# design.net
KiCad netlist of a schematic drawn in Altium Designer
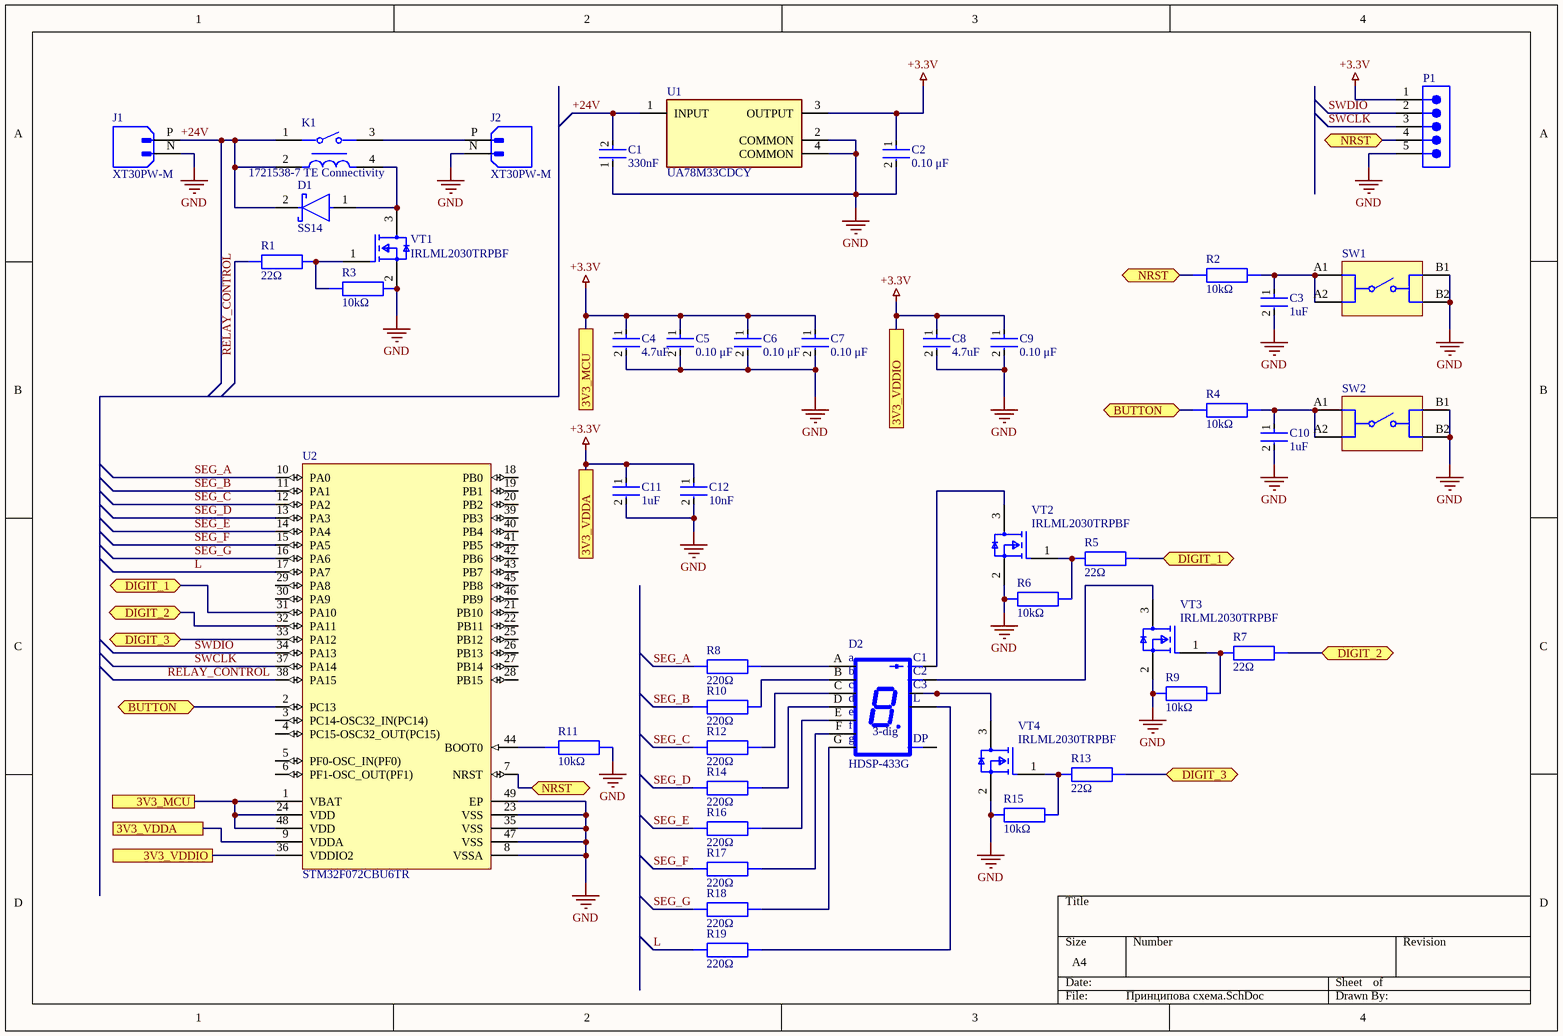
[diagram p0: Принципова схема.SchDoc]

(export (version "E")
  (design (tool "Eeschema 10.0.6"))
  (components
    (comp (ref "C1")
      (value "330nF")
      (footprint "FP-C1608-080-0_1-IPC_B")
      (description "Multilayer Ceramic Capacitors 330nF ±20% 35V X5R SMD 0603")
      (fields (field (name "TOLERANCE") "20%"))
      (libsource (lib "Altium Content Vault") (part "236180d848d6139a670b325ea6854c9"))
    )
    (comp (ref "C2")
      (value "0.10 μF")
      (footprint "FP-C0603C-CF-IPC_B")
      (description "CAP CER 0.1UF 50V X7R 0603")
      (fields
        (field (name "MANUFACTURER") "KEMET")
        (field (name "OCTOPART") "https://octopart.com/c0603c104j5racauto-kemet-18804944")
      )
      (libsource (lib "Altium Content Vault") (part "b4654b650e69147ec39a6b967a45e02"))
    )
    (comp (ref "C3")
      (value "1uF")
      (footprint "FP-0603-L_1_6_0_1-W_0_8_0-IPC_A")
      (description "None")
      (fields (field (name "TOLERANCE") "20%"))
      (libsource (lib "Altium Content Vault") (part "02cd4be3c70576c341d710602a673aa"))
    )
    (comp (ref "C4")
      (value "4.7uF")
      (footprint "FP-0603-L_1_6_0_1-W_0_8_0-IPC_B")
      (description "None")
      (fields (field (name "VOLTAGE") "6.3V") (field (name "TOLERANCE") "20%"))
      (libsource (lib "Altium Content Vault") (part "11868f565c42a9108669ba33697ecf6"))
    )
    (comp (ref "C5")
      (value "0.10 μF")
      (footprint "FP-C0603C-CF-IPC_B")
      (description "CAP CER 0.1UF 50V X7R 0603")
      (fields
        (field (name "MANUFACTURER") "KEMET")
        (field (name "OCTOPART") "https://octopart.com/c0603c104j5racauto-kemet-18804944")
      )
      (libsource (lib "Altium Content Vault") (part "b4654b650e69147ec39a6b967a45e02"))
    )
    (comp (ref "C6")
      (value "0.10 μF")
      (footprint "FP-C0603C-CF-IPC_B")
      (description "CAP CER 0.1UF 50V X7R 0603")
      (fields
        (field (name "MANUFACTURER") "KEMET")
        (field (name "OCTOPART") "https://octopart.com/c0603c104j5racauto-kemet-18804944")
      )
      (libsource (lib "Altium Content Vault") (part "b4654b650e69147ec39a6b967a45e02"))
    )
    (comp (ref "C7")
      (value "0.10 μF")
      (footprint "FP-C0603C-CF-IPC_B")
      (description "CAP CER 0.1UF 50V X7R 0603")
      (fields
        (field (name "MANUFACTURER") "KEMET")
        (field (name "OCTOPART") "https://octopart.com/c0603c104j5racauto-kemet-18804944")
      )
      (libsource (lib "Altium Content Vault") (part "b4654b650e69147ec39a6b967a45e02"))
    )
    (comp (ref "C8")
      (value "4.7uF")
      (footprint "FP-0603-L_1_6_0_1-W_0_8_0-IPC_B")
      (description "None")
      (fields (field (name "VOLTAGE") "6.3V") (field (name "TOLERANCE") "20%"))
      (libsource (lib "Altium Content Vault") (part "11868f565c42a9108669ba33697ecf6"))
    )
    (comp (ref "C9")
      (value "0.10 μF")
      (footprint "FP-C0603C-CF-IPC_B")
      (description "CAP CER 0.1UF 50V X7R 0603")
      (fields
        (field (name "MANUFACTURER") "KEMET")
        (field (name "OCTOPART") "https://octopart.com/c0603c104j5racauto-kemet-18804944")
      )
      (libsource (lib "Altium Content Vault") (part "b4654b650e69147ec39a6b967a45e02"))
    )
    (comp (ref "C10")
      (value "1uF")
      (footprint "FP-0603-L_1_6_0_1-W_0_8_0-IPC_A")
      (description "None")
      (fields (field (name "TOLERANCE") "20%"))
      (libsource (lib "Altium Content Vault") (part "02cd4be3c70576c341d710602a673aa"))
    )
    (comp (ref "C11")
      (value "1uF")
      (footprint "FP-0603-L_1_6_0_1-W_0_8_0-IPC_A")
      (description "None")
      (fields (field (name "TOLERANCE") "20%"))
      (libsource (lib "Altium Content Vault") (part "02cd4be3c70576c341d710602a673aa"))
    )
    (comp (ref "C12")
      (value "10nF")
      (footprint "FP-0603-L_1_6_0_1-W_0_8_0-IPC_A")
      (description "None")
      (fields (field (name "TOLERANCE") "10%"))
      (libsource (lib "Altium Content Vault") (part "02cd4be3c70576c341d710602a673aa"))
    )
    (comp (ref "D1")
      (value "SS14")
      (footprint "FP-403AE-MFG")
      (description "DIODE SCHOTTKY 40V 1A SMA")
      (fields
        (field (name "MANUFACTURER") "ON Semiconductor")
        (field (name "OCTOPART") "https://octopart.com/ss14-on+semiconductor-29205033")
      )
      (libsource (lib "Altium Content Vault") (part "360ad2f4ac25a952324d13796385471"))
    )
    (comp (ref "D2")
      (value "HDSP-433G")
      (footprint "HDSP-433G")
      (fields (field (name "MF") "Broadcom Limited") (field (name "DIGI-KEY_PART_NUMBER") "516-3125-ND"))
      (libsource (lib "HDSP-433G") (part "HDSP-433G"))
    )
    (comp (ref "J1")
      (value "XT30PW-M")
      (footprint "AMASS_XT30PW-M:AMASS_XT30PW-M")
      (description "Socket; DC supply; XT30; male; PIN: 2; on PCBs; THT; Colour: yellow")
      (fields (field (name "MANUFACTURER") "AMASS"))
      (libsource (lib "TestTask-Hardware") (part "XT30PW-M"))
    )
    (comp (ref "J2")
      (value "XT30PW-M")
      (footprint "AMASS_XT30PW-M:AMASS_XT30PW-M")
      (description "Socket; DC supply; XT30; male; PIN: 2; on PCBs; THT; Colour: yellow")
      (fields (field (name "MANUFACTURER") "AMASS"))
      (libsource (lib "") (part "XT30PW-M_1"))
    )
    (comp (ref "K1")
      (value "1721538-7 TE Connectivity")
      (footprint "FP-1721538-7-MFG")
      (description "RELAY GEN PURPOSE SPST10A 24V")
      (libsource (lib "Altium Content Vault") (part "efdf740da079d6e8343da2175463948"))
    )
    (comp (ref "P1")
      (value "~")
      (footprint "61300511121")
      (description "THT Vertical Pin Header WR-PHD, Pitch 2.54 mm, Single Row, 5 pins")
      (libsource (lib "Altium Content Vault") (part "Header_Male_1R_05P"))
    )
    (comp (ref "R1")
      (value "22Ω")
      (footprint "RES 0603_1608")
      (description "Fixed Resistor, Metal Glaze/Thick Film, 0.1W, 22ohm, 75V, 5% +/-Tol, Surface Mount, 0603")
      (fields
        (field (name "MANUFACTURER") "Vishay")
        (field (name "MANUFACTURER PART NUMBER") "CRCW060322R0JNTA")
      )
      (libsource (lib "Res") (part "Resistor"))
    )
    (comp (ref "R2")
      (value "10kΩ")
      (footprint "RES 0603_1608")
      (description "Res Thick Film 0603 10K Ohm 5% 0.1W(1/10W) ±200ppm/C Pad SMD Automotive T/R")
      (fields
        (field (name "MANUFACTURER") "Vishay")
        (field (name "MANUFACTURER PART NUMBER") "CRCW060310K0JNTA")
      )
      (libsource (lib "Res") (part "Resistor"))
    )
    (comp (ref "R3")
      (value "10kΩ")
      (footprint "RES 0603_1608")
      (description "Res Thick Film 0603 10K Ohm 5% 0.1W(1/10W) ±200ppm/C Pad SMD Automotive T/R")
      (fields
        (field (name "MANUFACTURER") "Vishay")
        (field (name "MANUFACTURER PART NUMBER") "CRCW060310K0JNTA")
      )
      (libsource (lib "Res") (part "Resistor"))
    )
    (comp (ref "R4")
      (value "10kΩ")
      (footprint "RES 0603_1608")
      (description "Res Thick Film 0603 10K Ohm 5% 0.1W(1/10W) ±200ppm/C Pad SMD Automotive T/R")
      (fields
        (field (name "MANUFACTURER") "Vishay")
        (field (name "MANUFACTURER PART NUMBER") "CRCW060310K0JNTA")
      )
      (libsource (lib "Res") (part "Resistor"))
    )
    (comp (ref "R5")
      (value "22Ω")
      (footprint "RES 0603_1608")
      (description "Fixed Resistor, Metal Glaze/Thick Film, 0.1W, 22ohm, 75V, 5% +/-Tol, Surface Mount, 0603")
      (fields
        (field (name "MANUFACTURER") "Vishay")
        (field (name "MANUFACTURER PART NUMBER") "CRCW060322R0JNTA")
      )
      (libsource (lib "Res") (part "Resistor"))
    )
    (comp (ref "R6")
      (value "10kΩ")
      (footprint "RES 0603_1608")
      (description "Res Thick Film 0603 10K Ohm 5% 0.1W(1/10W) ±200ppm/C Pad SMD Automotive T/R")
      (fields
        (field (name "MANUFACTURER") "Vishay")
        (field (name "MANUFACTURER PART NUMBER") "CRCW060310K0JNTA")
      )
      (libsource (lib "Res") (part "Resistor"))
    )
    (comp (ref "R7")
      (value "22Ω")
      (footprint "RES 0603_1608")
      (description "Fixed Resistor, Metal Glaze/Thick Film, 0.1W, 22ohm, 75V, 5% +/-Tol, Surface Mount, 0603")
      (fields
        (field (name "MANUFACTURER") "Vishay")
        (field (name "MANUFACTURER PART NUMBER") "CRCW060322R0JNTA")
      )
      (libsource (lib "Res") (part "Resistor"))
    )
    (comp (ref "R8")
      (value "220Ω")
      (footprint "RES 0603_1608")
      (description "Res Thick Film 0603 220 Ohm 1% 0.1W(1/10W) ±100ppm/C Pad SMD T/R Automotive AEC-Q200")
      (fields
        (field (name "MANUFACTURER") "Vishay")
        (field (name "MANUFACTURER PART NUMBER") "CRCW0603220RFKEC")
      )
      (libsource (lib "Res") (part "Resistor"))
    )
    (comp (ref "R9")
      (value "10kΩ")
      (footprint "RES 0603_1608")
      (description "Res Thick Film 0603 10K Ohm 5% 0.1W(1/10W) ±200ppm/C Pad SMD Automotive T/R")
      (fields
        (field (name "MANUFACTURER") "Vishay")
        (field (name "MANUFACTURER PART NUMBER") "CRCW060310K0JNTA")
      )
      (libsource (lib "Res") (part "Resistor"))
    )
    (comp (ref "R10")
      (value "220Ω")
      (footprint "RES 0603_1608")
      (description "Res Thick Film 0603 220 Ohm 1% 0.1W(1/10W) ±100ppm/C Pad SMD T/R Automotive AEC-Q200")
      (fields
        (field (name "MANUFACTURER") "Vishay")
        (field (name "MANUFACTURER PART NUMBER") "CRCW0603220RFKEC")
      )
      (libsource (lib "Res") (part "Resistor"))
    )
    (comp (ref "R11")
      (value "10kΩ")
      (footprint "RES 0603_1608")
      (description "Res Thick Film 0603 10K Ohm 5% 0.1W(1/10W) ±200ppm/C Pad SMD Automotive T/R")
      (fields
        (field (name "MANUFACTURER") "Vishay")
        (field (name "MANUFACTURER PART NUMBER") "CRCW060310K0JNTA")
      )
      (libsource (lib "Res") (part "Resistor"))
    )
    (comp (ref "R12")
      (value "220Ω")
      (footprint "RES 0603_1608")
      (description "Res Thick Film 0603 220 Ohm 1% 0.1W(1/10W) ±100ppm/C Pad SMD T/R Automotive AEC-Q200")
      (fields
        (field (name "MANUFACTURER") "Vishay")
        (field (name "MANUFACTURER PART NUMBER") "CRCW0603220RFKEC")
      )
      (libsource (lib "Res") (part "Resistor"))
    )
    (comp (ref "R13")
      (value "22Ω")
      (footprint "RES 0603_1608")
      (description "Fixed Resistor, Metal Glaze/Thick Film, 0.1W, 22ohm, 75V, 5% +/-Tol, Surface Mount, 0603")
      (fields
        (field (name "MANUFACTURER") "Vishay")
        (field (name "MANUFACTURER PART NUMBER") "CRCW060322R0JNTA")
      )
      (libsource (lib "Res") (part "Resistor"))
    )
    (comp (ref "R14")
      (value "220Ω")
      (footprint "RES 0603_1608")
      (description "Res Thick Film 0603 220 Ohm 1% 0.1W(1/10W) ±100ppm/C Pad SMD T/R Automotive AEC-Q200")
      (fields
        (field (name "MANUFACTURER") "Vishay")
        (field (name "MANUFACTURER PART NUMBER") "CRCW0603220RFKEC")
      )
      (libsource (lib "Res") (part "Resistor"))
    )
    (comp (ref "R15")
      (value "10kΩ")
      (footprint "RES 0603_1608")
      (description "Res Thick Film 0603 10K Ohm 5% 0.1W(1/10W) ±200ppm/C Pad SMD Automotive T/R")
      (fields
        (field (name "MANUFACTURER") "Vishay")
        (field (name "MANUFACTURER PART NUMBER") "CRCW060310K0JNTA")
      )
      (libsource (lib "Res") (part "Resistor"))
    )
    (comp (ref "R16")
      (value "220Ω")
      (footprint "RES 0603_1608")
      (description "Res Thick Film 0603 220 Ohm 1% 0.1W(1/10W) ±100ppm/C Pad SMD T/R Automotive AEC-Q200")
      (fields
        (field (name "MANUFACTURER") "Vishay")
        (field (name "MANUFACTURER PART NUMBER") "CRCW0603220RFKEC")
      )
      (libsource (lib "Res") (part "Resistor"))
    )
    (comp (ref "R17")
      (value "220Ω")
      (footprint "RES 0603_1608")
      (description "Res Thick Film 0603 220 Ohm 1% 0.1W(1/10W) ±100ppm/C Pad SMD T/R Automotive AEC-Q200")
      (fields
        (field (name "MANUFACTURER") "Vishay")
        (field (name "MANUFACTURER PART NUMBER") "CRCW0603220RFKEC")
      )
      (libsource (lib "Res") (part "Resistor"))
    )
    (comp (ref "R18")
      (value "220Ω")
      (footprint "RES 0603_1608")
      (description "Res Thick Film 0603 220 Ohm 1% 0.1W(1/10W) ±100ppm/C Pad SMD T/R Automotive AEC-Q200")
      (fields
        (field (name "MANUFACTURER") "Vishay")
        (field (name "MANUFACTURER PART NUMBER") "CRCW0603220RFKEC")
      )
      (libsource (lib "Res") (part "Resistor"))
    )
    (comp (ref "R19")
      (value "220Ω")
      (footprint "RES 0603_1608")
      (description "Res Thick Film 0603 220 Ohm 1% 0.1W(1/10W) ±100ppm/C Pad SMD T/R Automotive AEC-Q200")
      (fields
        (field (name "MANUFACTURER") "Vishay")
        (field (name "MANUFACTURER PART NUMBER") "CRCW0603220RFKEC")
      )
      (libsource (lib "Res") (part "Resistor"))
    )
    (comp (ref "SW1")
      (value "430162043826")
      (footprint "430162043826")
      (description "Tactile Switch, 0.05A, 12Vdc, 260Gf, Smd Rohs Compliant: Yes")
      (libsource (lib "Altium Content Vault") (part "SPST-NO_4P"))
    )
    (comp (ref "SW2")
      (value "430162043826")
      (footprint "430162043826")
      (description "Tactile Switch, 0.05A, 12Vdc, 260Gf, Smd Rohs Compliant: Yes")
      (libsource (lib "Altium Content Vault") (part "SPST-NO_4P"))
    )
    (comp (ref "U1")
      (value "UA78M33CDCY")
      (footprint "FP-DCY0004A-MFG")
      (description "IC REG LIN 3.3V 500MA SOT223-4")
      (fields
        (field (name "OCTOPART") "https://octopart.com/ua78m33cdcy-texas+instruments-1010398")
        (field (name "MANUFACTURER") "Texas Instruments")
      )
      (libsource (lib "Altium Content Vault") (part "be96c08bf657505148608e930dbb0d1"))
    )
    (comp (ref "U2")
      (value "STM32F072CBU6TR")
      (footprint "STM-UFQFPN48_L")
      (libsource (lib "Altium Content Vault") (part "MC-ARM-STM32F072-UFQFPN48"))
    )
    (comp (ref "VT1")
      (value "IRLML2030TRPBF")
      (footprint "FP-Micro3-MFG")
      (description "MOSFET N-CH 30V 2.7A SOT-23-3")
      (fields
        (field (name "OCTOPART") "https://octopart.com/irlml2030trpbf-infineon-65874966")
        (field (name "MANUFACTURER") "Infineon")
      )
      (libsource (lib "Altium Content Vault") (part "0a9ea7c96deaaede766a5b531c28de0"))
    )
    (comp (ref "VT2")
      (value "IRLML2030TRPBF")
      (footprint "FP-Micro3-MFG")
      (description "MOSFET N-CH 30V 2.7A SOT-23-3")
      (fields
        (field (name "OCTOPART") "https://octopart.com/irlml2030trpbf-infineon-65874966")
        (field (name "MANUFACTURER") "Infineon")
      )
      (libsource (lib "Altium Content Vault") (part "0a9ea7c96deaaede766a5b531c28de0"))
    )
    (comp (ref "VT3")
      (value "IRLML2030TRPBF")
      (footprint "FP-Micro3-MFG")
      (description "MOSFET N-CH 30V 2.7A SOT-23-3")
      (fields
        (field (name "OCTOPART") "https://octopart.com/irlml2030trpbf-infineon-65874966")
        (field (name "MANUFACTURER") "Infineon")
      )
      (libsource (lib "Altium Content Vault") (part "0a9ea7c96deaaede766a5b531c28de0"))
    )
    (comp (ref "VT4")
      (value "IRLML2030TRPBF")
      (footprint "FP-Micro3-MFG")
      (description "MOSFET N-CH 30V 2.7A SOT-23-3")
      (fields
        (field (name "OCTOPART") "https://octopart.com/irlml2030trpbf-infineon-65874966")
        (field (name "MANUFACTURER") "Infineon")
      )
      (libsource (lib "Altium Content Vault") (part "0a9ea7c96deaaede766a5b531c28de0"))
    )
  )
  (nets
    (net (code "1") (name "+3.3V") (class "Default")
      (node (ref "C11") (pin "1") (pinfunction "1_1") (pintype "passive"))
      (node (ref "C12") (pin "1") (pinfunction "1_1") (pintype "passive"))
      (node (ref "C2") (pin "1") (pinfunction "1_1") (pintype "passive"))
      (node (ref "C4") (pin "1") (pinfunction "1_1") (pintype "passive"))
      (node (ref "C5") (pin "1") (pinfunction "1_1") (pintype "passive"))
      (node (ref "C6") (pin "1") (pinfunction "1_1") (pintype "passive"))
      (node (ref "C7") (pin "1") (pinfunction "1_1") (pintype "passive"))
      (node (ref "C8") (pin "1") (pinfunction "1_1") (pintype "passive"))
      (node (ref "C9") (pin "1") (pinfunction "1_1") (pintype "passive"))
      (node (ref "P1") (pin "1") (pinfunction "1_1") (pintype "passive"))
      (node (ref "U1") (pin "3") (pinfunction "OUTPUT_3") (pintype "power_in"))
      (node (ref "U2") (pin "1") (pinfunction "VBAT_1") (pintype "power_in"))
      (node (ref "U2") (pin "24") (pinfunction "VDD_24") (pintype "power_in"))
      (node (ref "U2") (pin "36") (pinfunction "VDDIO2_36") (pintype "power_in"))
      (node (ref "U2") (pin "48") (pinfunction "VDD_48") (pintype "power_in"))
      (node (ref "U2") (pin "9") (pinfunction "VDDA_9") (pintype "power_in"))
    )
    (net (code "2") (name "/+24V") (class "Default")
      (node (ref "C1") (pin "2") (pinfunction "2_2") (pintype "passive"))
      (node (ref "D1") (pin "2") (pinfunction "C_2") (pintype "passive"))
      (node (ref "J1") (pin "P") (pinfunction "P_P") (pintype "power_in"))
      (node (ref "K1") (pin "1") (pinfunction "1_1") (pintype "passive"))
      (node (ref "K1") (pin "2") (pinfunction "2_2") (pintype "passive"))
      (node (ref "U1") (pin "1") (pinfunction "INPUT_1") (pintype "power_in"))
    )
    (net (code "3") (name "/BUTTON") (class "Default")
      (node (ref "R4") (pin "1") (pinfunction "1_1") (pintype "passive"))
      (node (ref "U2") (pin "2") (pinfunction "PC13_2") (pintype "bidirectional"))
    )
    (net (code "4") (name "/DIGIT_1") (class "Default")
      (node (ref "R5") (pin "2") (pinfunction "2_2") (pintype "passive"))
      (node (ref "U2") (pin "31") (pinfunction "PA10_31") (pintype "bidirectional"))
    )
    (net (code "5") (name "/DIGIT_2") (class "Default")
      (node (ref "R7") (pin "2") (pinfunction "2_2") (pintype "passive"))
      (node (ref "U2") (pin "32") (pinfunction "PA11_32") (pintype "bidirectional"))
    )
    (net (code "6") (name "/DIGIT_3") (class "Default")
      (node (ref "R13") (pin "2") (pinfunction "2_2") (pintype "passive"))
      (node (ref "U2") (pin "33") (pinfunction "PA12_33") (pintype "bidirectional"))
    )
    (net (code "7") (name "/L") (class "Default")
      (node (ref "R19") (pin "1") (pinfunction "1_1") (pintype "passive"))
      (node (ref "U2") (pin "17") (pinfunction "PA7_17") (pintype "bidirectional"))
    )
    (net (code "8") (name "/NRST") (class "Default")
      (node (ref "P1") (pin "4") (pinfunction "4_4") (pintype "passive"))
      (node (ref "R2") (pin "1") (pinfunction "1_1") (pintype "passive"))
      (node (ref "U2") (pin "7") (pinfunction "NRST_7") (pintype "bidirectional"))
    )
    (net (code "9") (name "/RELAY_CONTROL") (class "Default")
      (node (ref "R1") (pin "1") (pinfunction "1_1") (pintype "passive"))
      (node (ref "U2") (pin "38") (pinfunction "PA15_38") (pintype "bidirectional"))
    )
    (net (code "10") (name "/SEG_A") (class "Default")
      (node (ref "R8") (pin "1") (pinfunction "1_1") (pintype "passive"))
      (node (ref "U2") (pin "10") (pinfunction "PA0_10") (pintype "bidirectional"))
    )
    (net (code "11") (name "/SEG_B") (class "Default")
      (node (ref "R10") (pin "1") (pinfunction "1_1") (pintype "passive"))
      (node (ref "U2") (pin "11") (pinfunction "PA1_11") (pintype "bidirectional"))
    )
    (net (code "12") (name "/SEG_C") (class "Default")
      (node (ref "R12") (pin "1") (pinfunction "1_1") (pintype "passive"))
      (node (ref "U2") (pin "12") (pinfunction "PA2_12") (pintype "bidirectional"))
    )
    (net (code "13") (name "/SEG_D") (class "Default")
      (node (ref "R14") (pin "1") (pinfunction "1_1") (pintype "passive"))
      (node (ref "U2") (pin "13") (pinfunction "PA3_13") (pintype "bidirectional"))
    )
    (net (code "14") (name "/SEG_E") (class "Default")
      (node (ref "R16") (pin "1") (pinfunction "1_1") (pintype "passive"))
      (node (ref "U2") (pin "14") (pinfunction "PA4_14") (pintype "bidirectional"))
    )
    (net (code "15") (name "/SEG_F") (class "Default")
      (node (ref "R17") (pin "1") (pinfunction "1_1") (pintype "passive"))
      (node (ref "U2") (pin "15") (pinfunction "PA5_15") (pintype "bidirectional"))
    )
    (net (code "16") (name "/SEG_G") (class "Default")
      (node (ref "R18") (pin "1") (pinfunction "1_1") (pintype "passive"))
      (node (ref "U2") (pin "16") (pinfunction "PA6_16") (pintype "bidirectional"))
    )
    (net (code "17") (name "/SWCLK") (class "Default")
      (node (ref "P1") (pin "3") (pinfunction "3_3") (pintype "passive"))
      (node (ref "U2") (pin "37") (pinfunction "PA14_37") (pintype "bidirectional"))
    )
    (net (code "18") (name "/SWDIO") (class "Default")
      (node (ref "P1") (pin "2") (pinfunction "2_2") (pintype "passive"))
      (node (ref "U2") (pin "34") (pinfunction "PA13_34") (pintype "bidirectional"))
    )
    (net (code "19") (name "GND") (class "Default")
      (node (ref "C1") (pin "1") (pinfunction "1_1") (pintype "passive"))
      (node (ref "C10") (pin "2") (pinfunction "2_2") (pintype "passive"))
      (node (ref "C11") (pin "2") (pinfunction "2_2") (pintype "passive"))
      (node (ref "C12") (pin "2") (pinfunction "2_2") (pintype "passive"))
      (node (ref "C2") (pin "2") (pinfunction "2_2") (pintype "passive"))
      (node (ref "C3") (pin "2") (pinfunction "2_2") (pintype "passive"))
      (node (ref "C4") (pin "2") (pinfunction "2_2") (pintype "passive"))
      (node (ref "C5") (pin "2") (pinfunction "2_2") (pintype "passive"))
      (node (ref "C6") (pin "2") (pinfunction "2_2") (pintype "passive"))
      (node (ref "C7") (pin "2") (pinfunction "2_2") (pintype "passive"))
      (node (ref "C8") (pin "2") (pinfunction "2_2") (pintype "passive"))
      (node (ref "C9") (pin "2") (pinfunction "2_2") (pintype "passive"))
      (node (ref "J1") (pin "N") (pinfunction "N_N") (pintype "power_in"))
      (node (ref "J2") (pin "N") (pinfunction "N_N") (pintype "power_in"))
      (node (ref "P1") (pin "5") (pinfunction "5_5") (pintype "passive"))
      (node (ref "R11") (pin "2") (pinfunction "2_2") (pintype "passive"))
      (node (ref "R15") (pin "1") (pinfunction "1_1") (pintype "passive"))
      (node (ref "R3") (pin "2") (pinfunction "2_2") (pintype "passive"))
      (node (ref "R6") (pin "1") (pinfunction "1_1") (pintype "passive"))
      (node (ref "R9") (pin "1") (pinfunction "1_1") (pintype "passive"))
      (node (ref "SW1") (pin "B1") (pinfunction "B1_B1") (pintype "passive"))
      (node (ref "SW1") (pin "B2") (pinfunction "B2_B2") (pintype "passive"))
      (node (ref "SW2") (pin "B1") (pinfunction "B1_B1") (pintype "passive"))
      (node (ref "SW2") (pin "B2") (pinfunction "B2_B2") (pintype "passive"))
      (node (ref "U1") (pin "2") (pinfunction "COMMON_2") (pintype "power_in"))
      (node (ref "U1") (pin "4") (pinfunction "COMMON_4") (pintype "power_in"))
      (node (ref "U2") (pin "23") (pinfunction "VSS_23") (pintype "power_in"))
      (node (ref "U2") (pin "35") (pinfunction "VSS_35") (pintype "power_in"))
      (node (ref "U2") (pin "47") (pinfunction "VSS_47") (pintype "power_in"))
      (node (ref "U2") (pin "49") (pinfunction "EP_49") (pintype "power_in"))
      (node (ref "U2") (pin "8") (pinfunction "VSSA_8") (pintype "power_in"))
      (node (ref "VT1") (pin "2") (pinfunction "S_2") (pintype "passive"))
      (node (ref "VT2") (pin "2") (pinfunction "S_2") (pintype "passive"))
      (node (ref "VT3") (pin "2") (pinfunction "S_2") (pintype "passive"))
      (node (ref "VT4") (pin "2") (pinfunction "S_2") (pintype "passive"))
    )
    (net (code "20") (name "Net-(C3-Pad1)") (class "Default")
      (node (ref "C3") (pin "1") (pinfunction "1_1") (pintype "passive"))
      (node (ref "R2") (pin "2") (pinfunction "2_2") (pintype "passive"))
      (node (ref "SW1") (pin "A1") (pinfunction "A1_A1") (pintype "passive"))
      (node (ref "SW1") (pin "A2") (pinfunction "A2_A2") (pintype "passive"))
    )
    (net (code "21") (name "Net-(C10-Pad1)") (class "Default")
      (node (ref "C10") (pin "1") (pinfunction "1_1") (pintype "passive"))
      (node (ref "R4") (pin "2") (pinfunction "2_2") (pintype "passive"))
      (node (ref "SW2") (pin "A1") (pinfunction "A1_A1") (pintype "passive"))
      (node (ref "SW2") (pin "A2") (pinfunction "A2_A2") (pintype "passive"))
    )
    (net (code "22") (name "Net-(D1-A)") (class "Default")
      (node (ref "D1") (pin "1") (pinfunction "A_1") (pintype "passive"))
      (node (ref "K1") (pin "4") (pinfunction "4_4") (pintype "passive"))
      (node (ref "VT1") (pin "3") (pinfunction "D_3") (pintype "passive"))
    )
    (net (code "23") (name "Net-(D2-C1)") (class "Default")
      (node (ref "D2") (pin "D1") (pinfunction "C1_D1") (pintype "passive"))
      (node (ref "VT2") (pin "3") (pinfunction "D_3") (pintype "passive"))
    )
    (net (code "24") (name "Net-(D2-C2)") (class "Default")
      (node (ref "D2") (pin "D2") (pinfunction "C2_D2") (pintype "passive"))
      (node (ref "VT3") (pin "3") (pinfunction "D_3") (pintype "passive"))
    )
    (net (code "25") (name "Net-(D2-C3)") (class "Default")
      (node (ref "D2") (pin "D3") (pinfunction "C3_D3") (pintype "passive"))
      (node (ref "VT4") (pin "3") (pinfunction "D_3") (pintype "passive"))
    )
    (net (code "26") (name "Net-(D2-P$1)") (class "Default")
      (node (ref "D2") (pin "L") (pinfunction "P$1_L") (pintype "passive"))
      (node (ref "R19") (pin "2") (pinfunction "2_2") (pintype "passive"))
    )
    (net (code "27") (name "Net-(D2-PadA)") (class "Default")
      (node (ref "D2") (pin "A") (pinfunction "A_A") (pintype "passive"))
      (node (ref "R8") (pin "2") (pinfunction "2_2") (pintype "passive"))
    )
    (net (code "28") (name "Net-(D2-PadB)") (class "Default")
      (node (ref "D2") (pin "B") (pinfunction "B_B") (pintype "passive"))
      (node (ref "R10") (pin "2") (pinfunction "2_2") (pintype "passive"))
    )
    (net (code "29") (name "Net-(D2-PadC)") (class "Default")
      (node (ref "D2") (pin "C") (pinfunction "C_C") (pintype "passive"))
      (node (ref "R12") (pin "2") (pinfunction "2_2") (pintype "passive"))
    )
    (net (code "30") (name "Net-(D2-PadD)") (class "Default")
      (node (ref "D2") (pin "D") (pinfunction "D_D") (pintype "passive"))
      (node (ref "R14") (pin "2") (pinfunction "2_2") (pintype "passive"))
    )
    (net (code "31") (name "Net-(D2-PadE)") (class "Default")
      (node (ref "D2") (pin "E") (pinfunction "E_E") (pintype "passive"))
      (node (ref "R16") (pin "2") (pinfunction "2_2") (pintype "passive"))
    )
    (net (code "32") (name "Net-(D2-PadF)") (class "Default")
      (node (ref "D2") (pin "F") (pinfunction "F_F") (pintype "passive"))
      (node (ref "R17") (pin "2") (pinfunction "2_2") (pintype "passive"))
    )
    (net (code "33") (name "Net-(D2-PadG)") (class "Default")
      (node (ref "D2") (pin "G") (pinfunction "G_G") (pintype "passive"))
      (node (ref "R18") (pin "2") (pinfunction "2_2") (pintype "passive"))
    )
    (net (code "34") (name "Net-(J2-PadP)") (class "Default")
      (node (ref "J2") (pin "P") (pinfunction "P_P") (pintype "power_in"))
      (node (ref "K1") (pin "3") (pinfunction "3_3") (pintype "passive"))
    )
    (net (code "35") (name "Net-(U2-BOOT0)") (class "Default")
      (node (ref "R11") (pin "1") (pinfunction "1_1") (pintype "passive"))
      (node (ref "U2") (pin "44") (pinfunction "BOOT0_44") (pintype "input"))
    )
    (net (code "36") (name "Net-(VT1-G)") (class "Default")
      (node (ref "R1") (pin "2") (pinfunction "2_2") (pintype "passive"))
      (node (ref "R3") (pin "1") (pinfunction "1_1") (pintype "passive"))
      (node (ref "VT1") (pin "1") (pinfunction "G_1") (pintype "passive"))
    )
    (net (code "37") (name "Net-(VT2-G)") (class "Default")
      (node (ref "R5") (pin "1") (pinfunction "1_1") (pintype "passive"))
      (node (ref "R6") (pin "2") (pinfunction "2_2") (pintype "passive"))
      (node (ref "VT2") (pin "1") (pinfunction "G_1") (pintype "passive"))
    )
    (net (code "38") (name "Net-(VT3-G)") (class "Default")
      (node (ref "R7") (pin "1") (pinfunction "1_1") (pintype "passive"))
      (node (ref "R9") (pin "2") (pinfunction "2_2") (pintype "passive"))
      (node (ref "VT3") (pin "1") (pinfunction "G_1") (pintype "passive"))
    )
    (net (code "39") (name "Net-(VT4-G)") (class "Default")
      (node (ref "R13") (pin "1") (pinfunction "1_1") (pintype "passive"))
      (node (ref "R15") (pin "2") (pinfunction "2_2") (pintype "passive"))
      (node (ref "VT4") (pin "1") (pinfunction "G_1") (pintype "passive"))
    )
    (net (code "40") (name "unconnected-(D2-PadDP)") (class "Default")
      (node (ref "D2") (pin "DP") (pinfunction "DP_DP") (pintype "passive"))
    )
    (net (code "41") (name "unconnected-(U2-PA8-Pad29)") (class "Default")
      (node (ref "U2") (pin "29") (pinfunction "PA8_29") (pintype "bidirectional"))
    )
    (net (code "42") (name "unconnected-(U2-PA9-Pad30)") (class "Default")
      (node (ref "U2") (pin "30") (pinfunction "PA9_30") (pintype "bidirectional"))
    )
    (net (code "43") (name "unconnected-(U2-PB0-Pad18)") (class "Default")
      (node (ref "U2") (pin "18") (pinfunction "PB0_18") (pintype "bidirectional"))
    )
    (net (code "44") (name "unconnected-(U2-PB1-Pad19)") (class "Default")
      (node (ref "U2") (pin "19") (pinfunction "PB1_19") (pintype "bidirectional"))
    )
    (net (code "45") (name "unconnected-(U2-PB2-Pad20)") (class "Default")
      (node (ref "U2") (pin "20") (pinfunction "PB2_20") (pintype "bidirectional"))
    )
    (net (code "46") (name "unconnected-(U2-PB3-Pad39)") (class "Default")
      (node (ref "U2") (pin "39") (pinfunction "PB3_39") (pintype "bidirectional"))
    )
    (net (code "47") (name "unconnected-(U2-PB4-Pad40)") (class "Default")
      (node (ref "U2") (pin "40") (pinfunction "PB4_40") (pintype "bidirectional"))
    )
    (net (code "48") (name "unconnected-(U2-PB5-Pad41)") (class "Default")
      (node (ref "U2") (pin "41") (pinfunction "PB5_41") (pintype "bidirectional"))
    )
    (net (code "49") (name "unconnected-(U2-PB6-Pad42)") (class "Default")
      (node (ref "U2") (pin "42") (pinfunction "PB6_42") (pintype "bidirectional"))
    )
    (net (code "50") (name "unconnected-(U2-PB7-Pad43)") (class "Default")
      (node (ref "U2") (pin "43") (pinfunction "PB7_43") (pintype "bidirectional"))
    )
    (net (code "51") (name "unconnected-(U2-PB8-Pad45)") (class "Default")
      (node (ref "U2") (pin "45") (pinfunction "PB8_45") (pintype "bidirectional"))
    )
    (net (code "52") (name "unconnected-(U2-PB9-Pad46)") (class "Default")
      (node (ref "U2") (pin "46") (pinfunction "PB9_46") (pintype "bidirectional"))
    )
    (net (code "53") (name "unconnected-(U2-PB10-Pad21)") (class "Default")
      (node (ref "U2") (pin "21") (pinfunction "PB10_21") (pintype "bidirectional"))
    )
    (net (code "54") (name "unconnected-(U2-PB11-Pad22)") (class "Default")
      (node (ref "U2") (pin "22") (pinfunction "PB11_22") (pintype "bidirectional"))
    )
    (net (code "55") (name "unconnected-(U2-PB12-Pad25)") (class "Default")
      (node (ref "U2") (pin "25") (pinfunction "PB12_25") (pintype "bidirectional"))
    )
    (net (code "56") (name "unconnected-(U2-PB13-Pad26)") (class "Default")
      (node (ref "U2") (pin "26") (pinfunction "PB13_26") (pintype "bidirectional"))
    )
    (net (code "57") (name "unconnected-(U2-PB14-Pad27)") (class "Default")
      (node (ref "U2") (pin "27") (pinfunction "PB14_27") (pintype "bidirectional"))
    )
    (net (code "58") (name "unconnected-(U2-PB15-Pad28)") (class "Default")
      (node (ref "U2") (pin "28") (pinfunction "PB15_28") (pintype "bidirectional"))
    )
    (net (code "59") (name "unconnected-(U2-PC14-OSC32_IN(PC14)-Pad3)") (class "Default")
      (node (ref "U2") (pin "3") (pinfunction "PC14-OSC32_IN(PC14)_3") (pintype "bidirectional"))
    )
    (net (code "60") (name "unconnected-(U2-PC15-OSC32_OUT(PC15)-Pad4)") (class "Default")
      (node (ref "U2") (pin "4") (pinfunction "PC15-OSC32_OUT(PC15)_4") (pintype "bidirectional"))
    )
    (net (code "61") (name "unconnected-(U2-PF0-OSC_IN(PF0)-Pad5)") (class "Default")
      (node (ref "U2") (pin "5") (pinfunction "PF0-OSC_IN(PF0)_5") (pintype "bidirectional"))
    )
    (net (code "62") (name "unconnected-(U2-PF1-OSC_OUT(PF1)-Pad6)") (class "Default")
      (node (ref "U2") (pin "6") (pinfunction "PF1-OSC_OUT(PF1)_6") (pintype "bidirectional"))
    )
  )
)
